# Suply.net
KiCad netlist of a schematic drawn in Altium Designer
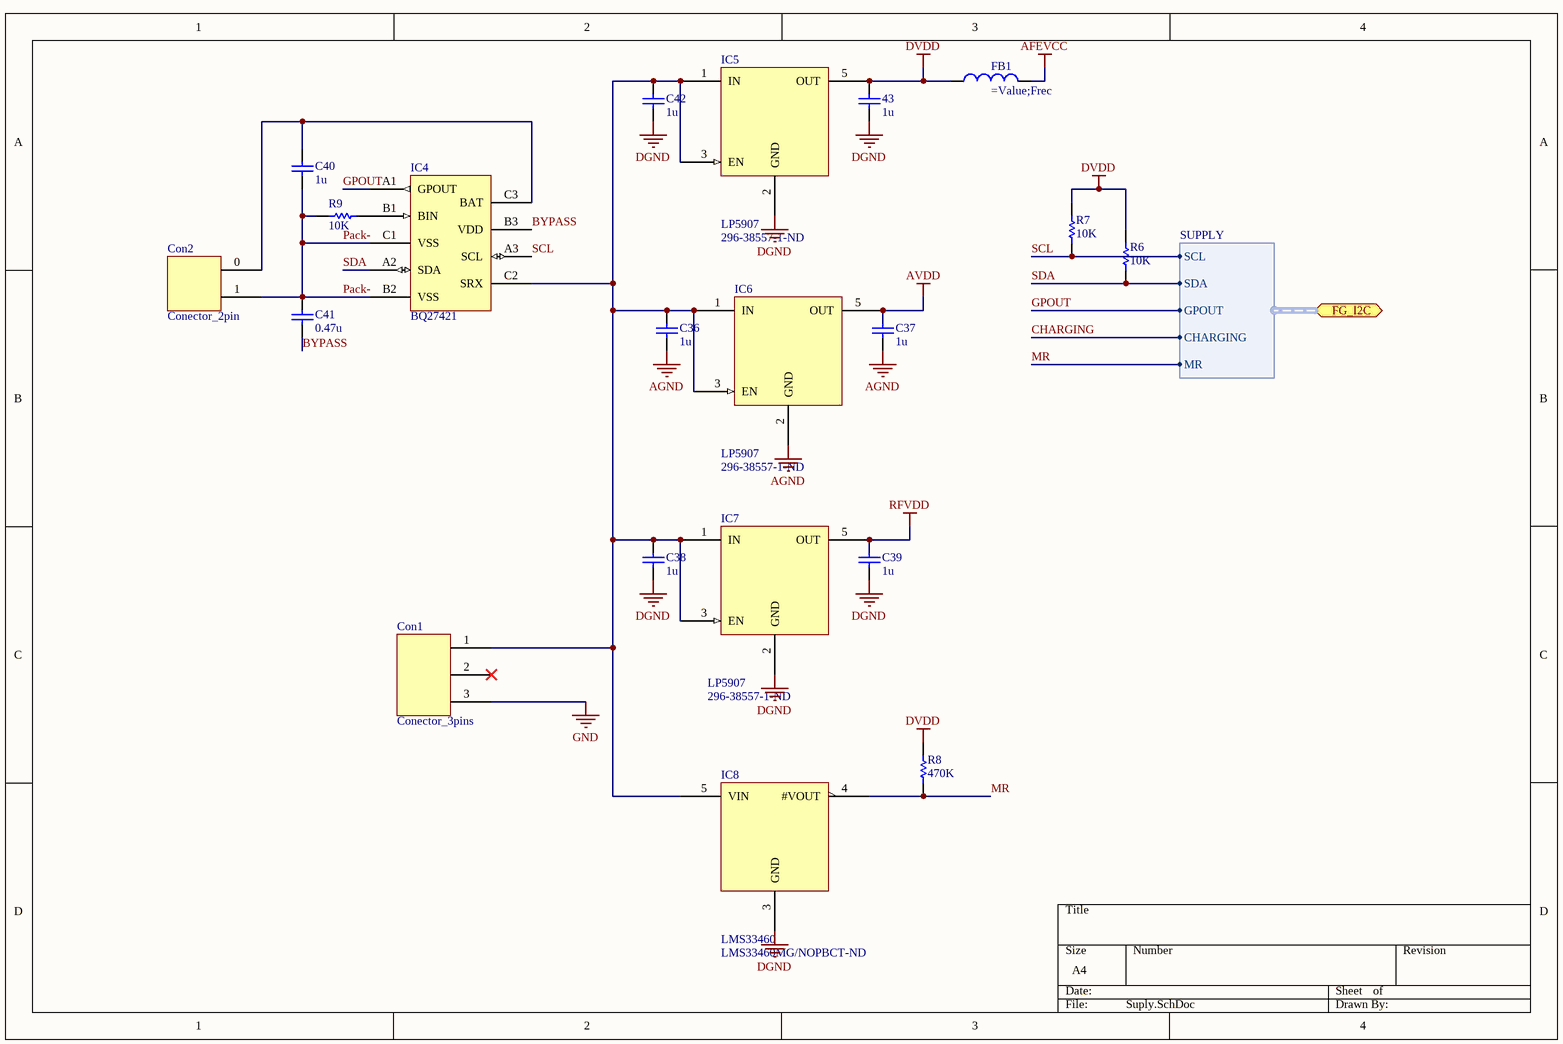
[diagram p0: Suply.SchDoc]

(export (version "E")
  (design (tool "Eeschema 10.0.6"))
  (components
    (comp (ref "43")
      (value "1u")
      (footprint "C0805")
      (description "Capacitor")
      (libsource (lib "Common Devices") (part "Capacitor"))
    )
    (comp (ref "C36")
      (value "1u")
      (footprint "C0805")
      (description "Capacitor")
      (libsource (lib "Common Devices") (part "Capacitor"))
    )
    (comp (ref "C37")
      (value "1u")
      (footprint "C0805")
      (description "Capacitor")
      (libsource (lib "Common Devices") (part "Capacitor"))
    )
    (comp (ref "C38")
      (value "1u")
      (footprint "C0805")
      (description "Capacitor")
      (libsource (lib "Common Devices") (part "Capacitor"))
    )
    (comp (ref "C39")
      (value "1u")
      (footprint "C0805")
      (description "Capacitor")
      (libsource (lib "Common Devices") (part "Capacitor"))
    )
    (comp (ref "C40")
      (value "1u")
      (footprint "C0805")
      (description "Capacitor")
      (libsource (lib "Common Devices") (part "Capacitor"))
    )
    (comp (ref "C41")
      (value "0.47u")
      (footprint "C0805")
      (description "Capacitor")
      (libsource (lib "Common Devices") (part "Capacitor"))
    )
    (comp (ref "C42")
      (value "1u")
      (footprint "C0805")
      (description "Capacitor")
      (libsource (lib "Common Devices") (part "Capacitor"))
    )
    (comp (ref "Con1")
      (value "Conector_3pins")
      (description "Conector")
      (libsource (lib "Common Devices") (part "Conector_3pins"))
    )
    (comp (ref "Con2") (value "Conector_2pin") (libsource (lib "Common Devices") (part "Conector_2pin")))
    (comp (ref "FB1")
      (value "~")
      (footprint "INDUCTOR-5MM")
      (description "Ferrite")
      (libsource (lib "Common Devices") (part "Ferrite"))
    )
    (comp (ref "IC4") (value "BQ27421") (footprint "BQ27421") (libsource (lib "Main Board") (part "BQ27421")))
    (comp (ref "IC5")
      (value "LP5907")
      (footprint "SOT95P280X145-5N")
      (fields (field (name "SUPPLIER PART NUMBER 1") "296-38557-1-ND"))
      (libsource (lib "Main Board") (part "LP5907"))
    )
    (comp (ref "IC6")
      (value "LP5907")
      (footprint "SOT95P280X145-5N")
      (fields (field (name "SUPPLIER PART NUMBER 1") "296-38557-1-ND"))
      (libsource (lib "Main Board") (part "LP5907"))
    )
    (comp (ref "IC7")
      (value "LP5907")
      (footprint "SOT95P280X145-5N")
      (fields (field (name "SUPPLIER PART NUMBER 1") "296-38557-1-ND"))
      (libsource (lib "Main Board") (part "LP5907"))
    )
    (comp (ref "IC8")
      (value "LMS33460")
      (footprint "SOT65P210X110-5N")
      (fields (field (name "SUPPLIER PART NUMBER 1") "LMS33460MG/NOPBCT-ND"))
      (libsource (lib "Main Board") (part "LMS33460"))
    )
    (comp (ref "R6")
      (value "10K")
      (footprint "R0805")
      (description "Resistor")
      (libsource (lib "Common Devices") (part "Resistor"))
    )
    (comp (ref "R7")
      (value "10K")
      (footprint "R0805")
      (description "Resistor")
      (libsource (lib "Common Devices") (part "Resistor"))
    )
    (comp (ref "R8")
      (value "470K")
      (footprint "R0805")
      (description "Resistor")
      (libsource (lib "Common Devices") (part "Resistor"))
    )
    (comp (ref "R9")
      (value "10K")
      (footprint "R0805")
      (description "Resistor")
      (libsource (lib "Common Devices") (part "Resistor"))
    )
  )
  (nets
    (net (code "2") (name "/BYPASS") (class "Default")
      (node (ref "C41") (pin "1") (pinfunction "1_1") (pintype "passive"))
      (node (ref "IC4") (pin "B3") (pinfunction "VDD_B3") (pintype "power_in"))
    )
    (net (code "4") (name "/GPOUT") (class "Default")
      (node (ref "IC4") (pin "A1") (pinfunction "GPOUT_A1") (pintype "output"))
    )
    (net (code "5") (name "/MR") (class "Default")
      (node (ref "IC8") (pin "4") (pinfunction "#VOUT_4") (pintype "open_collector"))
      (node (ref "R8") (pin "1") (pinfunction "1_1") (pintype "passive"))
    )
    (net (code "6") (name "/Pack-") (class "Default")
      (node (ref "C40") (pin "1") (pinfunction "1_1") (pintype "passive"))
      (node (ref "C41") (pin "2") (pinfunction "2_2") (pintype "passive"))
      (node (ref "Con2") (pin "1") (pinfunction "1_1") (pintype "passive"))
      (node (ref "IC4") (pin "B2") (pinfunction "VSS_B2") (pintype "power_in"))
      (node (ref "IC4") (pin "C1") (pinfunction "VSS_C1") (pintype "power_in"))
      (node (ref "R9") (pin "1") (pinfunction "1_1") (pintype "passive"))
    )
    (net (code "7") (name "/SCL") (class "Default")
      (node (ref "IC4") (pin "A3") (pinfunction "SCL_A3") (pintype "bidirectional"))
      (node (ref "R7") (pin "1") (pinfunction "1_1") (pintype "passive"))
    )
    (net (code "8") (name "/SDA") (class "Default")
      (node (ref "IC4") (pin "A2") (pinfunction "SDA_A2") (pintype "bidirectional"))
      (node (ref "R6") (pin "1") (pinfunction "1_1") (pintype "passive"))
    )
    (net (code "10") (name "AFEVCC") (class "Default")
      (node (ref "FB1") (pin "2") (pinfunction "2_2") (pintype "passive"))
    )
    (net (code "11") (name "AGND") (class "Default")
      (node (ref "C36") (pin "1") (pinfunction "1_1") (pintype "passive"))
      (node (ref "C37") (pin "1") (pinfunction "1_1") (pintype "passive"))
      (node (ref "IC6") (pin "2") (pinfunction "GND_2") (pintype "power_in"))
    )
    (net (code "12") (name "AVDD") (class "Default")
      (node (ref "C37") (pin "2") (pinfunction "2_2") (pintype "passive"))
      (node (ref "IC6") (pin "5") (pinfunction "OUT_5") (pintype "power_in"))
    )
    (net (code "13") (name "DGND") (class "Default")
      (node (ref "43") (pin "1") (pinfunction "1_1") (pintype "passive"))
      (node (ref "C38") (pin "1") (pinfunction "1_1") (pintype "passive"))
      (node (ref "C39") (pin "1") (pinfunction "1_1") (pintype "passive"))
      (node (ref "C42") (pin "1") (pinfunction "1_1") (pintype "passive"))
      (node (ref "IC5") (pin "2") (pinfunction "GND_2") (pintype "power_in"))
      (node (ref "IC7") (pin "2") (pinfunction "GND_2") (pintype "power_in"))
      (node (ref "IC8") (pin "3") (pinfunction "GND_3") (pintype "power_in"))
    )
    (net (code "14") (name "DVDD") (class "Default")
      (node (ref "43") (pin "2") (pinfunction "2_2") (pintype "passive"))
      (node (ref "FB1") (pin "1") (pinfunction "1_1") (pintype "passive"))
      (node (ref "IC5") (pin "5") (pinfunction "OUT_5") (pintype "power_in"))
      (node (ref "R6") (pin "2") (pinfunction "2_2") (pintype "passive"))
      (node (ref "R7") (pin "2") (pinfunction "2_2") (pintype "passive"))
      (node (ref "R8") (pin "2") (pinfunction "2_2") (pintype "passive"))
    )
    (net (code "15") (name "GND") (class "Default")
      (node (ref "Con1") (pin "3") (pinfunction "3_3") (pintype "passive"))
    )
    (net (code "16") (name "Net-(IC4-BAT)") (class "Default")
      (node (ref "C40") (pin "2") (pinfunction "2_2") (pintype "passive"))
      (node (ref "Con2") (pin "0") (pinfunction "0_0") (pintype "passive"))
      (node (ref "IC4") (pin "C3") (pinfunction "BAT_C3") (pintype "power_in"))
    )
    (net (code "17") (name "Net-(IC4-BIN)") (class "Default")
      (node (ref "IC4") (pin "B1") (pinfunction "BIN_B1") (pintype "input"))
      (node (ref "R9") (pin "2") (pinfunction "2_2") (pintype "passive"))
    )
    (net (code "18") (name "Net-(IC4-SRX)") (class "Default")
      (node (ref "C36") (pin "2") (pinfunction "2_2") (pintype "passive"))
      (node (ref "C38") (pin "2") (pinfunction "2_2") (pintype "passive"))
      (node (ref "C42") (pin "2") (pinfunction "2_2") (pintype "passive"))
      (node (ref "Con1") (pin "1") (pinfunction "1_1") (pintype "passive"))
      (node (ref "IC4") (pin "C2") (pinfunction "SRX_C2") (pintype "power_in"))
      (node (ref "IC5") (pin "1") (pinfunction "IN_1") (pintype "power_in"))
      (node (ref "IC5") (pin "3") (pinfunction "EN_3") (pintype "input"))
      (node (ref "IC6") (pin "1") (pinfunction "IN_1") (pintype "power_in"))
      (node (ref "IC6") (pin "3") (pinfunction "EN_3") (pintype "input"))
      (node (ref "IC7") (pin "1") (pinfunction "IN_1") (pintype "power_in"))
      (node (ref "IC7") (pin "3") (pinfunction "EN_3") (pintype "input"))
      (node (ref "IC8") (pin "5") (pinfunction "VIN_5") (pintype "power_in"))
    )
    (net (code "19") (name "RFVDD") (class "Default")
      (node (ref "C39") (pin "2") (pinfunction "2_2") (pintype "passive"))
      (node (ref "IC7") (pin "5") (pinfunction "OUT_5") (pintype "power_in"))
    )
    (net (code "20") (name "unconnected-(Con1-Pad2)") (class "Default")
      (node (ref "Con1") (pin "2") (pinfunction "2_2") (pintype "passive+no_connect"))
    )
  )
)
